# ESP8266-DS18B20-lite.net
KiCad netlist of a schematic drawn in EAGLE
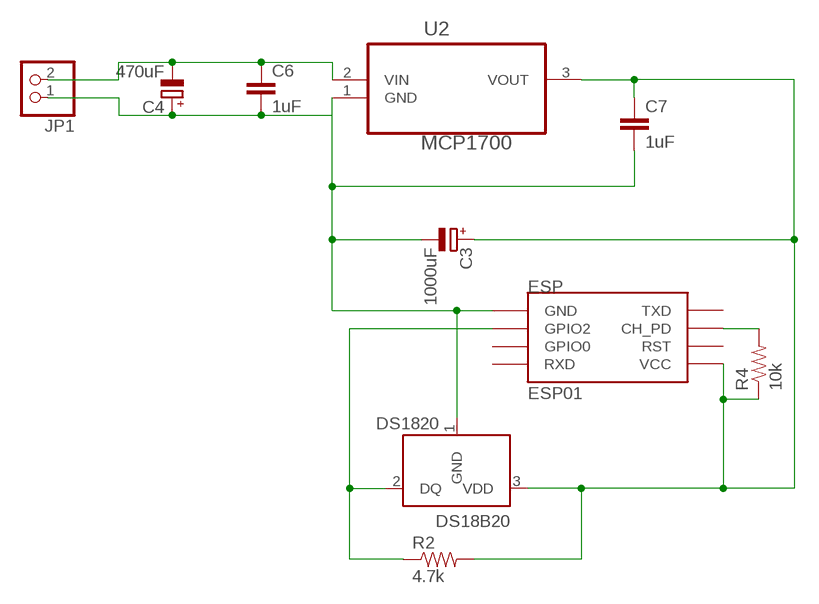
[diagram p0: schematic, sheet 1]

(export (version "E")
  (design (tool "Eeschema 10.0.6"))
  (components
    (comp (ref "C3")
      (value "1000uF")
      (footprint "eagle-import:E2,5-5")
      (libsource (lib "eagle-import") (part "CPOL-EUE2.5-5"))
    )
    (comp (ref "C4")
      (value "470uF")
      (footprint "eagle-import:E2,5-5")
      (libsource (lib "eagle-import") (part "CPOL-EUE2.5-5"))
    )
    (comp (ref "C6")
      (value "1uF")
      (footprint "eagle-import:CAP-PTH-SMALLEZ")
      (libsource (lib "eagle-import") (part "CAPEZ"))
    )
    (comp (ref "C7")
      (value "1uF")
      (footprint "eagle-import:CAP-PTH-SMALLEZ")
      (libsource (lib "eagle-import") (part "CAPEZ"))
    )
    (comp (ref "DS18B20")
      (value "DS1820")
      (footprint "eagle-import:TO-92")
      (libsource (lib "eagle-import") (part "DS1820"))
    )
    (comp (ref "ESP")
      (value "ESP01")
      (footprint "eagle-import:ESP01")
      (libsource (lib "eagle-import") (part "ESP01"))
    )
    (comp (ref "JP1")
      (value "PINHD-1X2/90")
      (footprint "eagle-import:1X02_90")
      (libsource (lib "eagle-import") (part "PINHD-1X2/90"))
    )
    (comp (ref "R2")
      (value "4.7k")
      (footprint "eagle-import:AXIAL-0.3")
      (libsource (lib "eagle-import") (part "RESISTORAXIAL-0.3"))
    )
    (comp (ref "R4")
      (value "10k")
      (footprint "eagle-import:AXIAL-0.3")
      (libsource (lib "eagle-import") (part "RESISTORAXIAL-0.3"))
    )
    (comp (ref "U2")
      (value "MCP1700")
      (footprint "eagle-import:TO127P254X495-3")
      (fields (field (name "MPN") "MCP1700-3302E/TO"))
      (libsource (lib "eagle-import") (part "MCP1700-3302E/TO"))
    )
  )
  (nets
    (net (code "1") (name "Net-(DS18B20-DQ)") (class "Default")
      (node (ref "DS18B20") (pin "2") (pinfunction "DQ_2") (pintype "output"))
      (node (ref "ESP") (pin "GPIO2") (pinfunction "GPIO2_GPIO2") (pintype "bidirectional"))
      (node (ref "R2") (pin "P$1") (pinfunction "1_P$1") (pintype "passive"))
    )
    (net (code "2") (name "Net-(DS18B20-GND)") (class "Default")
      (node (ref "C3") (pin "-") (pinfunction "-_-") (pintype "passive"))
      (node (ref "C4") (pin "+") (pinfunction "+_+") (pintype "passive"))
      (node (ref "C6") (pin "2") (pinfunction "2_2") (pintype "passive"))
      (node (ref "C7") (pin "2") (pinfunction "2_2") (pintype "passive"))
      (node (ref "DS18B20") (pin "1") (pinfunction "GND_1") (pintype "power_in"))
      (node (ref "ESP") (pin "GND") (pinfunction "GND_GND") (pintype "bidirectional"))
      (node (ref "JP1") (pin "1") (pinfunction "1_1") (pintype "passive"))
      (node (ref "U2") (pin "1") (pinfunction "GND_1") (pintype "passive"))
    )
    (net (code "3") (name "Net-(DS18B20-VDD)") (class "Default")
      (node (ref "C3") (pin "+") (pinfunction "+_+") (pintype "passive"))
      (node (ref "C7") (pin "1") (pinfunction "1_1") (pintype "passive"))
      (node (ref "DS18B20") (pin "3") (pinfunction "VDD_3") (pintype "input"))
      (node (ref "ESP") (pin "VCC") (pinfunction "VCC_VCC") (pintype "bidirectional"))
      (node (ref "R2") (pin "P$2") (pinfunction "2_P$2") (pintype "passive"))
      (node (ref "R4") (pin "P$1") (pinfunction "1_P$1") (pintype "passive"))
      (node (ref "U2") (pin "3") (pinfunction "VOUT_3") (pintype "output"))
    )
    (net (code "4") (name "Net-(R4-2)") (class "Default")
      (node (ref "ESP") (pin "CH_PD") (pinfunction "CH_PD_CH_PD") (pintype "bidirectional"))
      (node (ref "R4") (pin "P$2") (pinfunction "2_P$2") (pintype "passive"))
    )
    (net (code "5") (name "Net-(U2-VIN)") (class "Default")
      (node (ref "C4") (pin "-") (pinfunction "-_-") (pintype "passive"))
      (node (ref "C6") (pin "1") (pinfunction "1_1") (pintype "passive"))
      (node (ref "JP1") (pin "2") (pinfunction "2_2") (pintype "passive"))
      (node (ref "U2") (pin "2") (pinfunction "VIN_2") (pintype "input"))
    )
    (net (code "6") (name "unconnected-(ESP-PadGPIO0)") (class "Default")
      (node (ref "ESP") (pin "GPIO0") (pinfunction "GPIO0_GPIO0") (pintype "bidirectional"))
    )
    (net (code "7") (name "unconnected-(ESP-PadRST)") (class "Default")
      (node (ref "ESP") (pin "RST") (pinfunction "RST_RST") (pintype "bidirectional"))
    )
    (net (code "8") (name "unconnected-(ESP-RXD-PadRX)") (class "Default")
      (node (ref "ESP") (pin "RX") (pinfunction "RXD_RX") (pintype "bidirectional"))
    )
    (net (code "9") (name "unconnected-(ESP-TXD-PadTX)") (class "Default")
      (node (ref "ESP") (pin "TX") (pinfunction "TXD_TX") (pintype "bidirectional"))
    )
  )
)
